# LTC2473CDR1.net
KiCad netlist of a schematic drawn in EAGLE
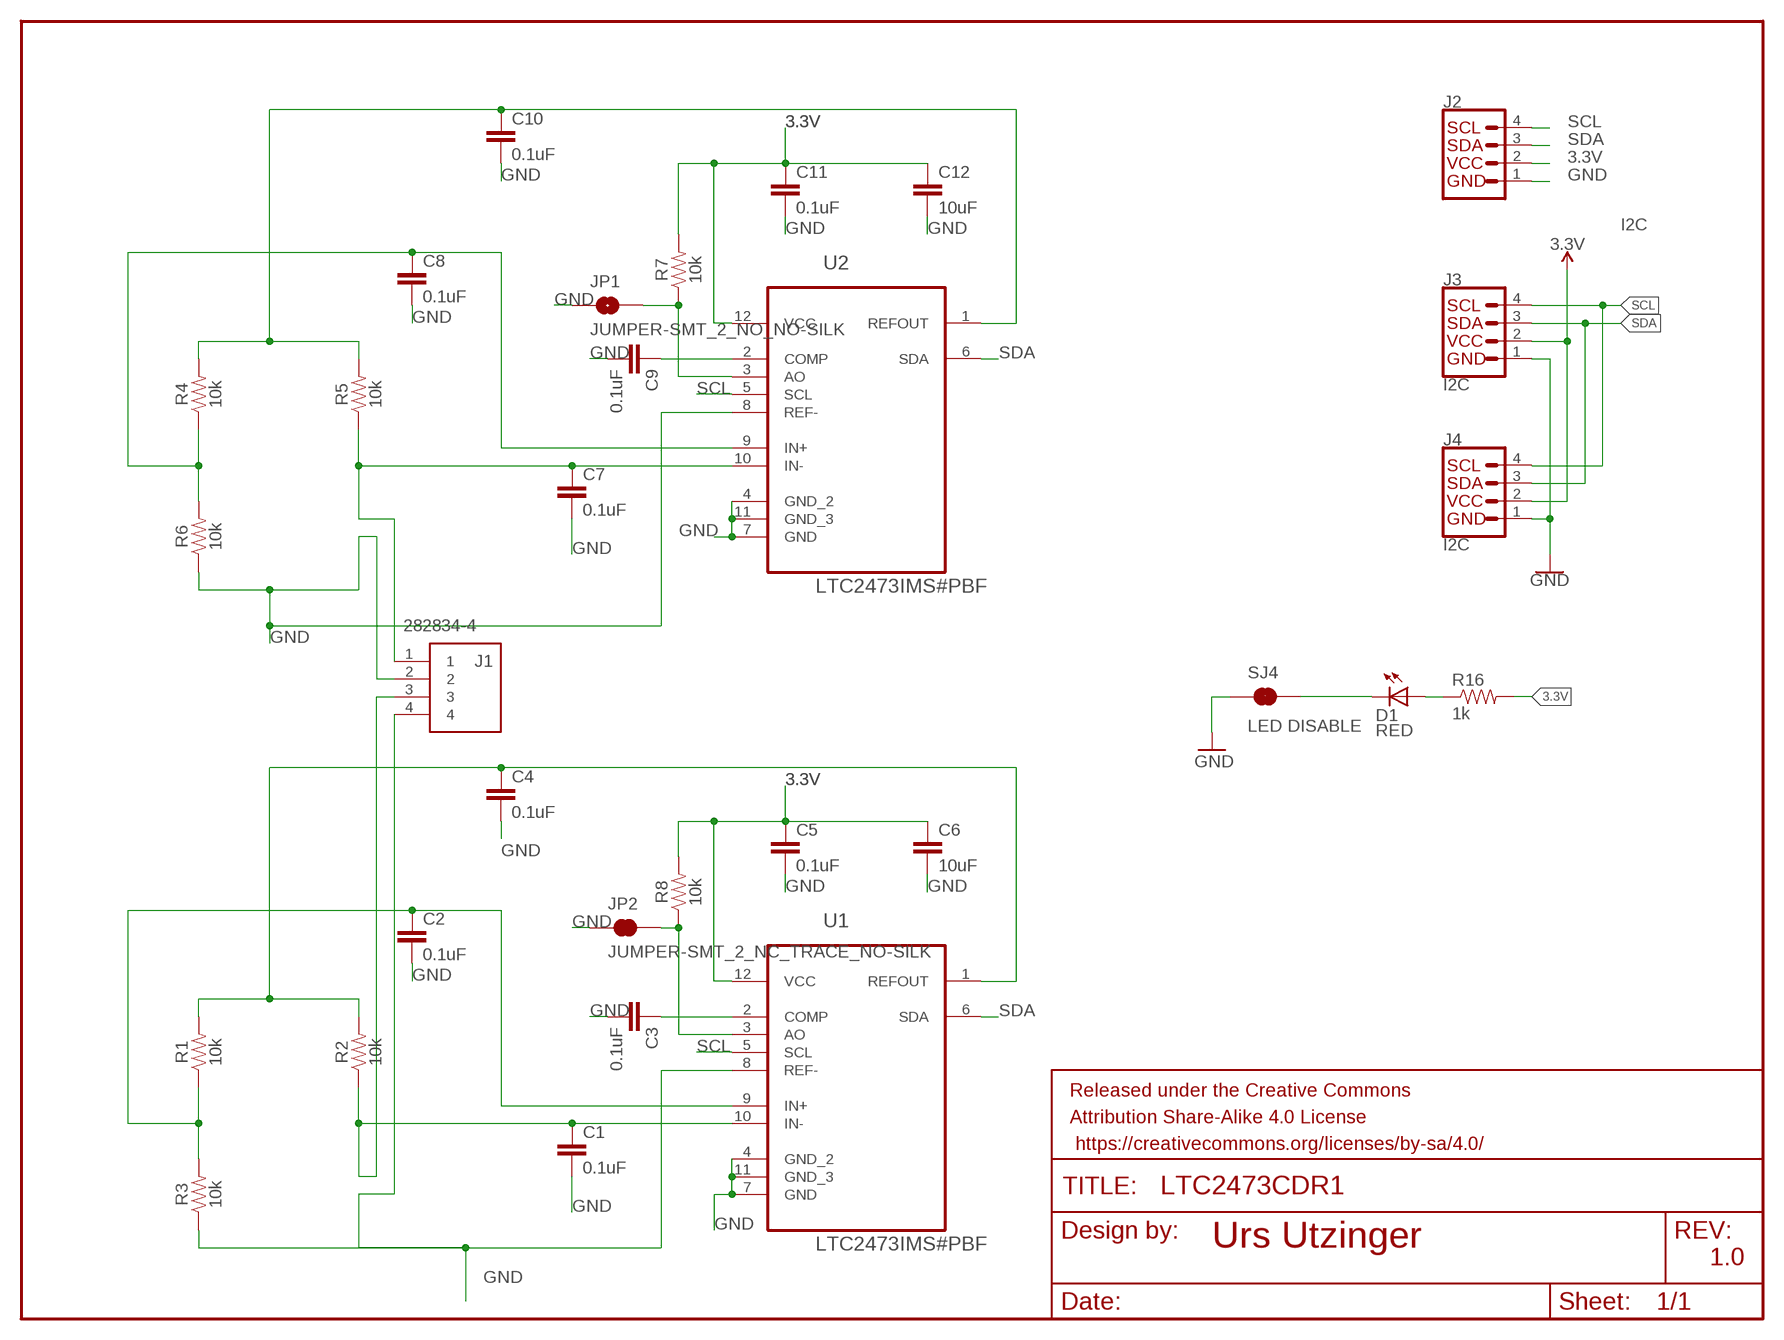
[diagram p0: schematic, sheet 1]

(export (version "E")
  (design (tool "Eeschema 10.0.6"))
  (components
    (comp (ref "C1")
      (value "0.1uF")
      (footprint "eagle-import:0603")
      (libsource (lib "eagle-import") (part "0.1UF-0603-25V-(+80/-20%)"))
    )
    (comp (ref "C2")
      (value "0.1uF")
      (footprint "eagle-import:0603")
      (libsource (lib "eagle-import") (part "0.1UF-0603-25V-(+80/-20%)"))
    )
    (comp (ref "C3")
      (value "0.1uF")
      (footprint "eagle-import:0603")
      (libsource (lib "eagle-import") (part "0.1UF-0603-25V-(+80/-20%)"))
    )
    (comp (ref "C4")
      (value "0.1uF")
      (footprint "eagle-import:0603")
      (libsource (lib "eagle-import") (part "0.1UF-0603-25V-(+80/-20%)"))
    )
    (comp (ref "C5")
      (value "0.1uF")
      (footprint "eagle-import:0603")
      (libsource (lib "eagle-import") (part "0.1UF-0603-25V-(+80/-20%)"))
    )
    (comp (ref "C6")
      (value "10uF")
      (footprint "eagle-import:0603")
      (libsource (lib "eagle-import") (part "10UF-0603-6.3V-20%"))
    )
    (comp (ref "C7")
      (value "0.1uF")
      (footprint "eagle-import:0603")
      (libsource (lib "eagle-import") (part "0.1UF-0603-25V-(+80/-20%)"))
    )
    (comp (ref "C8")
      (value "0.1uF")
      (footprint "eagle-import:0603")
      (libsource (lib "eagle-import") (part "0.1UF-0603-25V-(+80/-20%)"))
    )
    (comp (ref "C9")
      (value "0.1uF")
      (footprint "eagle-import:0603")
      (libsource (lib "eagle-import") (part "0.1UF-0603-25V-(+80/-20%)"))
    )
    (comp (ref "C10")
      (value "0.1uF")
      (footprint "eagle-import:0603")
      (libsource (lib "eagle-import") (part "0.1UF-0603-25V-(+80/-20%)"))
    )
    (comp (ref "C11")
      (value "0.1uF")
      (footprint "eagle-import:0603")
      (libsource (lib "eagle-import") (part "0.1UF-0603-25V-(+80/-20%)"))
    )
    (comp (ref "C12")
      (value "10uF")
      (footprint "eagle-import:0603")
      (libsource (lib "eagle-import") (part "10UF-0603-6.3V-20%"))
    )
    (comp (ref "D1")
      (value "RED")
      (footprint "eagle-import:LED-0603")
      (libsource (lib "eagle-import") (part "LED-RED0603"))
    )
    (comp (ref "FRAME1")
      (value "FRAME-LETTERNO_PACKAGE")
      (footprint "eagle-import:DUMMY")
      (fields (field (name "DESIGNER") "Nobody"))
      (libsource (lib "eagle-import") (part "FRAME-LETTERNO_PACKAGE"))
    )
    (comp (ref "J1")
      (value "282834-4")
      (footprint "eagle-import:2828344")
      (fields (field (name "MOUSER_PART_NUMBER") "571-282834-4"))
      (libsource (lib "eagle-import") (part "282834-4"))
    )
    (comp (ref "J2")
      (value "I2C")
      (footprint "eagle-import:1X04")
      (libsource (lib "eagle-import") (part "I2C_STANDARD"))
    )
    (comp (ref "J3")
      (value "I2C")
      (footprint "eagle-import:JST04_1MM_RA")
      (libsource (lib "eagle-import") (part "QWIIC_CONNECTORJS-1MM"))
    )
    (comp (ref "J4")
      (value "I2C")
      (footprint "eagle-import:JST04_1MM_RA")
      (libsource (lib "eagle-import") (part "QWIIC_CONNECTORJS-1MM"))
    )
    (comp (ref "JP1")
      (value "JUMPER-SMT_2_NO_NO-SILK")
      (footprint "eagle-import:SMT-JUMPER_2_NO_NO-SILK")
      (libsource (lib "eagle-import") (part "JUMPER-SMT_2_NO_NO-SILK"))
    )
    (comp (ref "JP2")
      (value "JUMPER-SMT_2_NC_TRACE_NO-SILK")
      (footprint "eagle-import:SMT-JUMPER_2_NC_TRACE_NO-SILK")
      (libsource (lib "eagle-import") (part "JUMPER-SMT_2_NC_TRACE_NO-SILK"))
    )
    (comp (ref "R1")
      (value "10k")
      (footprint "eagle-import:0603")
      (libsource (lib "eagle-import") (part "10KOHM-0603-1/10W-1%"))
    )
    (comp (ref "R2")
      (value "10k")
      (footprint "eagle-import:0603")
      (libsource (lib "eagle-import") (part "10KOHM-0603-1/10W-1%"))
    )
    (comp (ref "R3")
      (value "10k")
      (footprint "eagle-import:0603")
      (libsource (lib "eagle-import") (part "10KOHM-0603-1/10W-1%"))
    )
    (comp (ref "R4")
      (value "10k")
      (footprint "eagle-import:0603")
      (libsource (lib "eagle-import") (part "10KOHM-0603-1/10W-1%"))
    )
    (comp (ref "R5")
      (value "10k")
      (footprint "eagle-import:0603")
      (libsource (lib "eagle-import") (part "10KOHM-0603-1/10W-1%"))
    )
    (comp (ref "R6")
      (value "10k")
      (footprint "eagle-import:0603")
      (libsource (lib "eagle-import") (part "10KOHM-0603-1/10W-1%"))
    )
    (comp (ref "R7")
      (value "10k")
      (footprint "eagle-import:0603")
      (libsource (lib "eagle-import") (part "10KOHM-0603-1/10W-1%"))
    )
    (comp (ref "R8")
      (value "10k")
      (footprint "eagle-import:0603")
      (libsource (lib "eagle-import") (part "10KOHM-0603-1/10W-1%"))
    )
    (comp (ref "R16")
      (value "1k")
      (footprint "eagle-import:0603")
      (libsource (lib "eagle-import") (part "1KOHM-0603-1/10W-1%"))
    )
    (comp (ref "SJ4")
      (value "LED DISABLE")
      (footprint "eagle-import:SMT-JUMPER_2_NC_TRACE_NO-SILK")
      (libsource (lib "eagle-import") (part "JUMPER-SMT_2_NC_TRACE_NO-SILK"))
    )
    (comp (ref "U1")
      (value "LTC2473IMS#PBF")
      (footprint "eagle-import:SOP65P490X110-12N")
      (fields (field (name "MF") "Analog Devices"))
      (libsource (lib "eagle-import") (part "LTC2473IMS#PBF"))
    )
    (comp (ref "U2")
      (value "LTC2473IMS#PBF")
      (footprint "eagle-import:SOP65P490X110-12N")
      (fields (field (name "MF") "Analog Devices"))
      (libsource (lib "eagle-import") (part "LTC2473IMS#PBF"))
    )
  )
  (nets
    (net (code "1") (name "3.3V") (class "Default")
      (node (ref "C11") (pin "1") (pinfunction "1_1") (pintype "passive"))
      (node (ref "C12") (pin "1") (pinfunction "1_1") (pintype "passive"))
      (node (ref "C5") (pin "1") (pinfunction "1_1") (pintype "passive"))
      (node (ref "C6") (pin "1") (pinfunction "1_1") (pintype "passive"))
      (node (ref "J2") (pin "2") (pinfunction "2_2") (pintype "power_in"))
      (node (ref "J3") (pin "2") (pinfunction "2_2") (pintype "power_in"))
      (node (ref "J4") (pin "2") (pinfunction "2_2") (pintype "power_in"))
      (node (ref "R16") (pin "2") (pinfunction "2_2") (pintype "passive"))
      (node (ref "R7") (pin "2") (pinfunction "2_2") (pintype "passive"))
      (node (ref "R8") (pin "2") (pinfunction "2_2") (pintype "passive"))
      (node (ref "U1") (pin "12") (pinfunction "VCC_12") (pintype "power_in"))
      (node (ref "U2") (pin "12") (pinfunction "VCC_12") (pintype "power_in"))
    )
    (net (code "2") (name "GND") (class "Default")
      (node (ref "C1") (pin "2") (pinfunction "2_2") (pintype "passive"))
      (node (ref "C10") (pin "2") (pinfunction "2_2") (pintype "passive"))
      (node (ref "C11") (pin "2") (pinfunction "2_2") (pintype "passive"))
      (node (ref "C12") (pin "2") (pinfunction "2_2") (pintype "passive"))
      (node (ref "C2") (pin "2") (pinfunction "2_2") (pintype "passive"))
      (node (ref "C3") (pin "2") (pinfunction "2_2") (pintype "passive"))
      (node (ref "C4") (pin "2") (pinfunction "2_2") (pintype "passive"))
      (node (ref "C5") (pin "2") (pinfunction "2_2") (pintype "passive"))
      (node (ref "C6") (pin "2") (pinfunction "2_2") (pintype "passive"))
      (node (ref "C7") (pin "2") (pinfunction "2_2") (pintype "passive"))
      (node (ref "C8") (pin "2") (pinfunction "2_2") (pintype "passive"))
      (node (ref "C9") (pin "2") (pinfunction "2_2") (pintype "passive"))
      (node (ref "J1") (pin "2") (pinfunction "2_2") (pintype "bidirectional"))
      (node (ref "J1") (pin "4") (pinfunction "4_4") (pintype "bidirectional"))
      (node (ref "J2") (pin "1") (pinfunction "1_1") (pintype "power_in"))
      (node (ref "J3") (pin "1") (pinfunction "1_1") (pintype "power_in"))
      (node (ref "J4") (pin "1") (pinfunction "1_1") (pintype "power_in"))
      (node (ref "JP1") (pin "1") (pinfunction "1_1") (pintype "passive"))
      (node (ref "JP2") (pin "1") (pinfunction "1_1") (pintype "passive"))
      (node (ref "R3") (pin "1") (pinfunction "1_1") (pintype "passive"))
      (node (ref "R6") (pin "1") (pinfunction "1_1") (pintype "passive"))
      (node (ref "SJ4") (pin "1") (pinfunction "1_1") (pintype "passive"))
      (node (ref "U1") (pin "11") (pinfunction "GND_3_11") (pintype "passive"))
      (node (ref "U1") (pin "4") (pinfunction "GND_2_4") (pintype "passive"))
      (node (ref "U1") (pin "7") (pinfunction "GND_7") (pintype "passive"))
      (node (ref "U1") (pin "8") (pinfunction "REF-_8") (pintype "input"))
      (node (ref "U2") (pin "11") (pinfunction "GND_3_11") (pintype "passive"))
      (node (ref "U2") (pin "4") (pinfunction "GND_2_4") (pintype "passive"))
      (node (ref "U2") (pin "7") (pinfunction "GND_7") (pintype "passive"))
      (node (ref "U2") (pin "8") (pinfunction "REF-_8") (pintype "input"))
    )
    (net (code "3") (name "Net-(D1-PadA)") (class "Default")
      (node (ref "D1") (pin "A") (pinfunction "A_A") (pintype "passive"))
      (node (ref "R16") (pin "1") (pinfunction "1_1") (pintype "passive"))
    )
    (net (code "4") (name "Net-(D1-PadC)") (class "Default")
      (node (ref "D1") (pin "C") (pinfunction "C_C") (pintype "passive"))
      (node (ref "SJ4") (pin "2") (pinfunction "2_2") (pintype "passive"))
    )
    (net (code "5") (name "Net-(U1-AO)") (class "Default")
      (node (ref "JP2") (pin "2") (pinfunction "2_2") (pintype "passive"))
      (node (ref "R8") (pin "1") (pinfunction "1_1") (pintype "passive"))
      (node (ref "U1") (pin "3") (pinfunction "AO_3") (pintype "input"))
    )
    (net (code "6") (name "Net-(U1-COMP)") (class "Default")
      (node (ref "C3") (pin "1") (pinfunction "1_1") (pintype "passive"))
      (node (ref "U1") (pin "2") (pinfunction "COMP_2") (pintype "input"))
    )
    (net (code "7") (name "Net-(U1-IN+)") (class "Default")
      (node (ref "C2") (pin "1") (pinfunction "1_1") (pintype "passive"))
      (node (ref "R1") (pin "1") (pinfunction "1_1") (pintype "passive"))
      (node (ref "R3") (pin "2") (pinfunction "2_2") (pintype "passive"))
      (node (ref "U1") (pin "9") (pinfunction "IN+_9") (pintype "input"))
    )
    (net (code "8") (name "Net-(U1-IN-)") (class "Default")
      (node (ref "C1") (pin "1") (pinfunction "1_1") (pintype "passive"))
      (node (ref "J1") (pin "3") (pinfunction "3_3") (pintype "bidirectional"))
      (node (ref "R2") (pin "1") (pinfunction "1_1") (pintype "passive"))
      (node (ref "U1") (pin "10") (pinfunction "IN-_10") (pintype "input"))
    )
    (net (code "9") (name "Net-(U1-REFOUT)") (class "Default")
      (node (ref "C4") (pin "1") (pinfunction "1_1") (pintype "passive"))
      (node (ref "R1") (pin "2") (pinfunction "2_2") (pintype "passive"))
      (node (ref "R2") (pin "2") (pinfunction "2_2") (pintype "passive"))
      (node (ref "U1") (pin "1") (pinfunction "REFOUT_1") (pintype "output"))
    )
    (net (code "10") (name "Net-(U2-AO)") (class "Default")
      (node (ref "JP1") (pin "2") (pinfunction "2_2") (pintype "passive"))
      (node (ref "R7") (pin "1") (pinfunction "1_1") (pintype "passive"))
      (node (ref "U2") (pin "3") (pinfunction "AO_3") (pintype "input"))
    )
    (net (code "11") (name "Net-(U2-COMP)") (class "Default")
      (node (ref "C9") (pin "1") (pinfunction "1_1") (pintype "passive"))
      (node (ref "U2") (pin "2") (pinfunction "COMP_2") (pintype "input"))
    )
    (net (code "12") (name "Net-(U2-IN+)") (class "Default")
      (node (ref "C8") (pin "1") (pinfunction "1_1") (pintype "passive"))
      (node (ref "R4") (pin "1") (pinfunction "1_1") (pintype "passive"))
      (node (ref "R6") (pin "2") (pinfunction "2_2") (pintype "passive"))
      (node (ref "U2") (pin "9") (pinfunction "IN+_9") (pintype "input"))
    )
    (net (code "13") (name "Net-(U2-IN-)") (class "Default")
      (node (ref "C7") (pin "1") (pinfunction "1_1") (pintype "passive"))
      (node (ref "J1") (pin "1") (pinfunction "1_1") (pintype "bidirectional"))
      (node (ref "R5") (pin "1") (pinfunction "1_1") (pintype "passive"))
      (node (ref "U2") (pin "10") (pinfunction "IN-_10") (pintype "input"))
    )
    (net (code "14") (name "Net-(U2-REFOUT)") (class "Default")
      (node (ref "C10") (pin "1") (pinfunction "1_1") (pintype "passive"))
      (node (ref "R4") (pin "2") (pinfunction "2_2") (pintype "passive"))
      (node (ref "R5") (pin "2") (pinfunction "2_2") (pintype "passive"))
      (node (ref "U2") (pin "1") (pinfunction "REFOUT_1") (pintype "output"))
    )
    (net (code "15") (name "SCL") (class "Default")
      (node (ref "J2") (pin "4") (pinfunction "4_4") (pintype "passive"))
      (node (ref "J3") (pin "4") (pinfunction "4_4") (pintype "passive"))
      (node (ref "J4") (pin "4") (pinfunction "4_4") (pintype "passive"))
      (node (ref "U1") (pin "5") (pinfunction "SCL_5") (pintype "input"))
      (node (ref "U2") (pin "5") (pinfunction "SCL_5") (pintype "input"))
    )
    (net (code "16") (name "SDA") (class "Default")
      (node (ref "J2") (pin "3") (pinfunction "3_3") (pintype "passive"))
      (node (ref "J3") (pin "3") (pinfunction "3_3") (pintype "passive"))
      (node (ref "J4") (pin "3") (pinfunction "3_3") (pintype "passive"))
      (node (ref "U1") (pin "6") (pinfunction "SDA_6") (pintype "bidirectional"))
      (node (ref "U2") (pin "6") (pinfunction "SDA_6") (pintype "bidirectional"))
    )
  )
)
